# 2_Microcontroller.net
KiCad netlist of a schematic drawn in Altium Designer
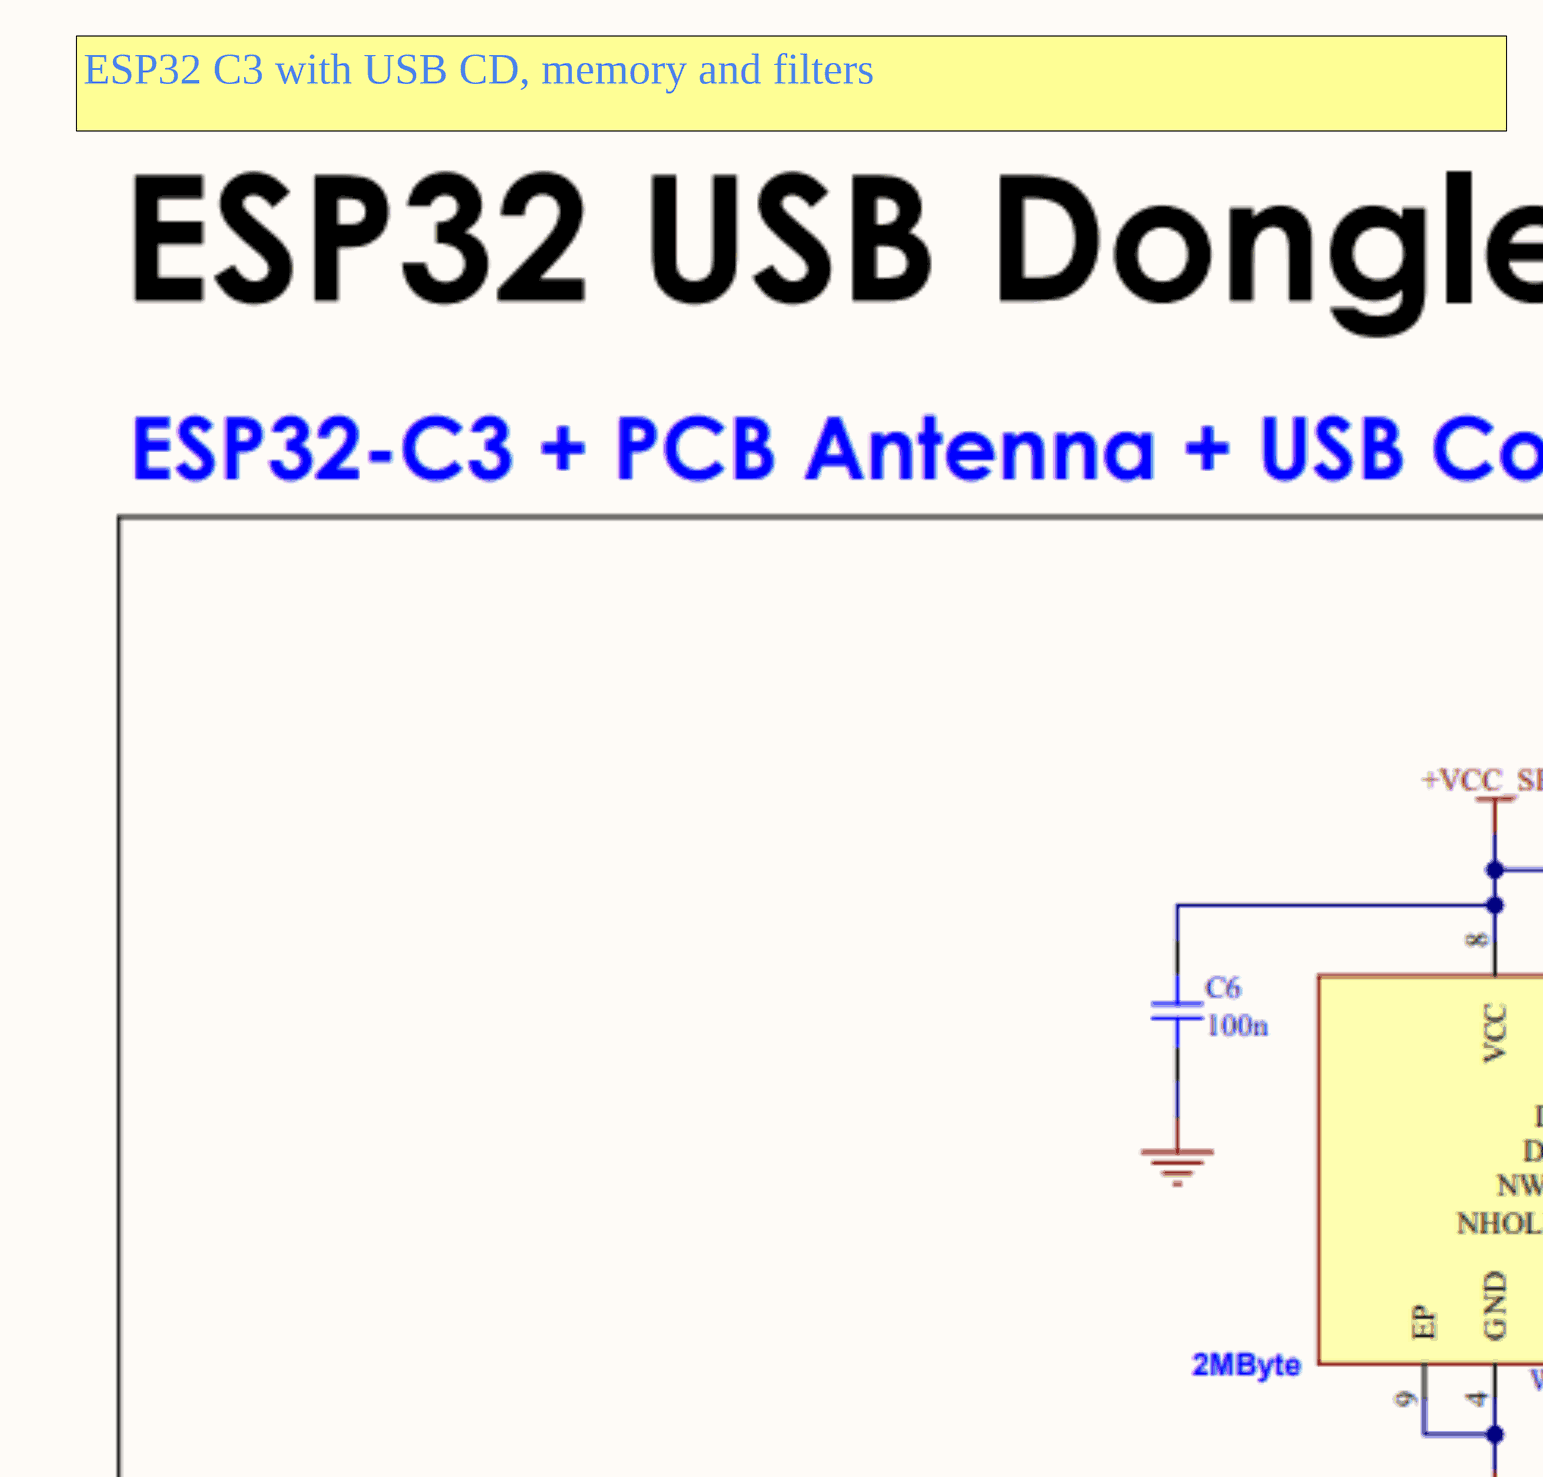
[diagram p0: 2_Microcontroller.SchDoc, top right]
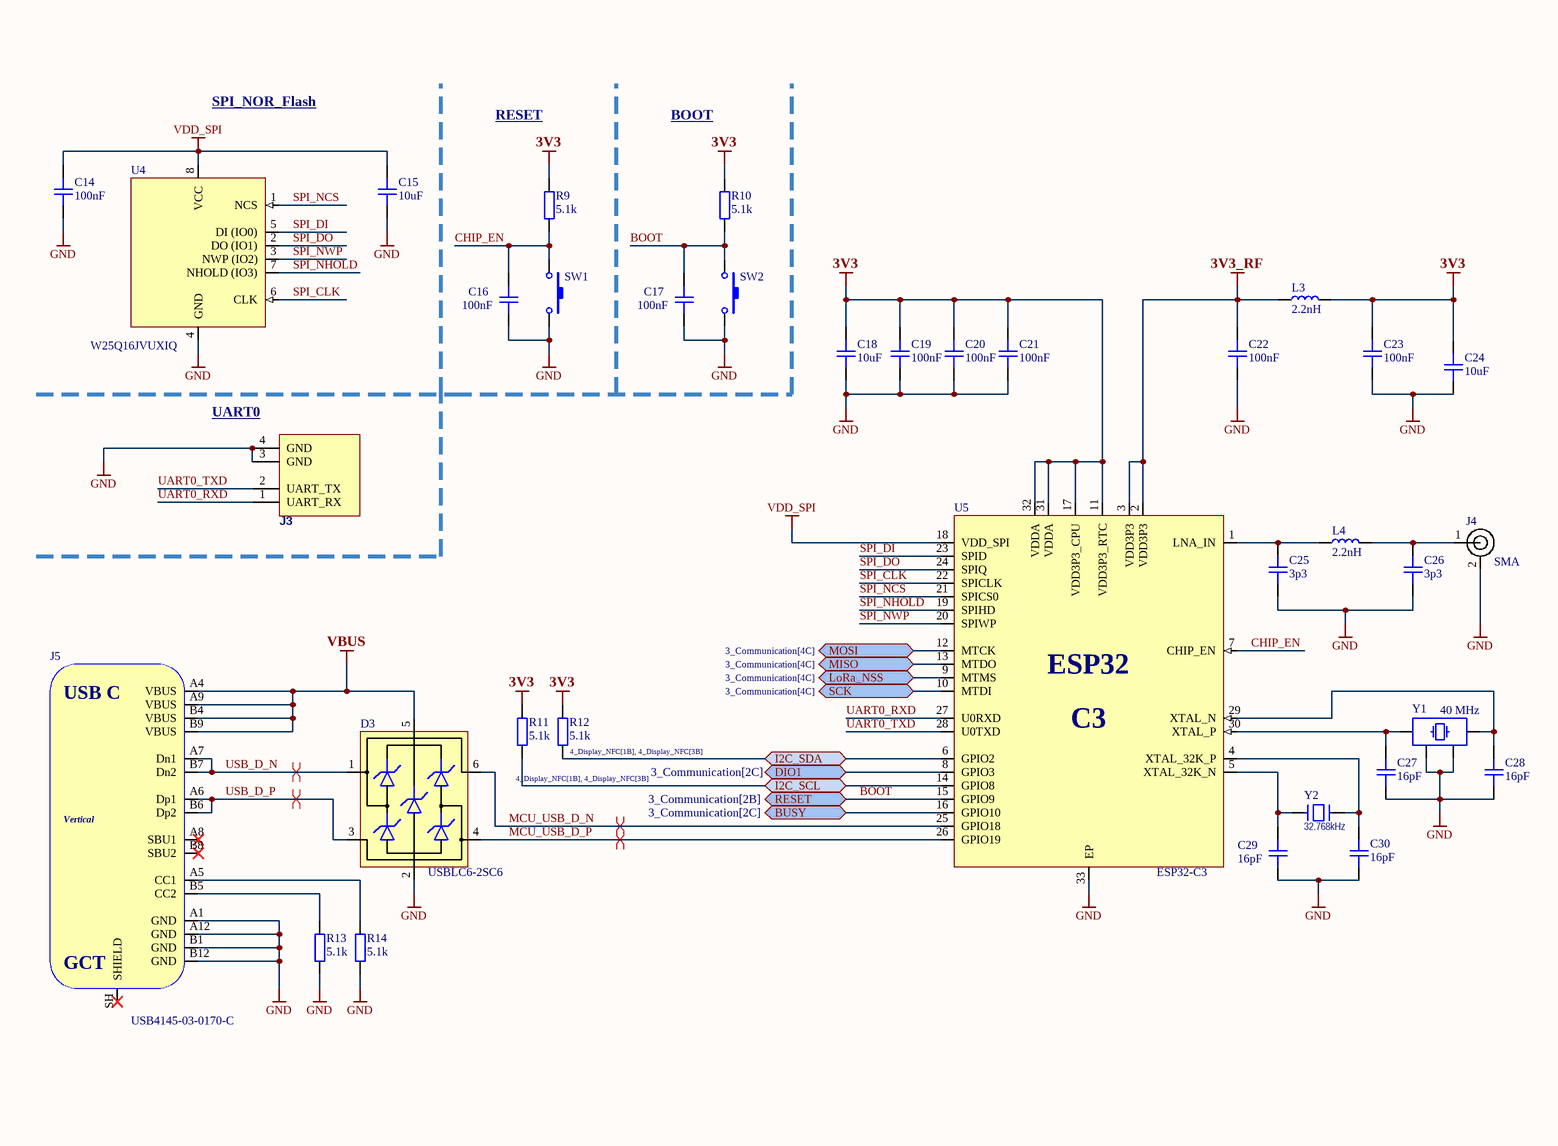
[diagram p1: 2_Microcontroller.SchDoc, bottom left]
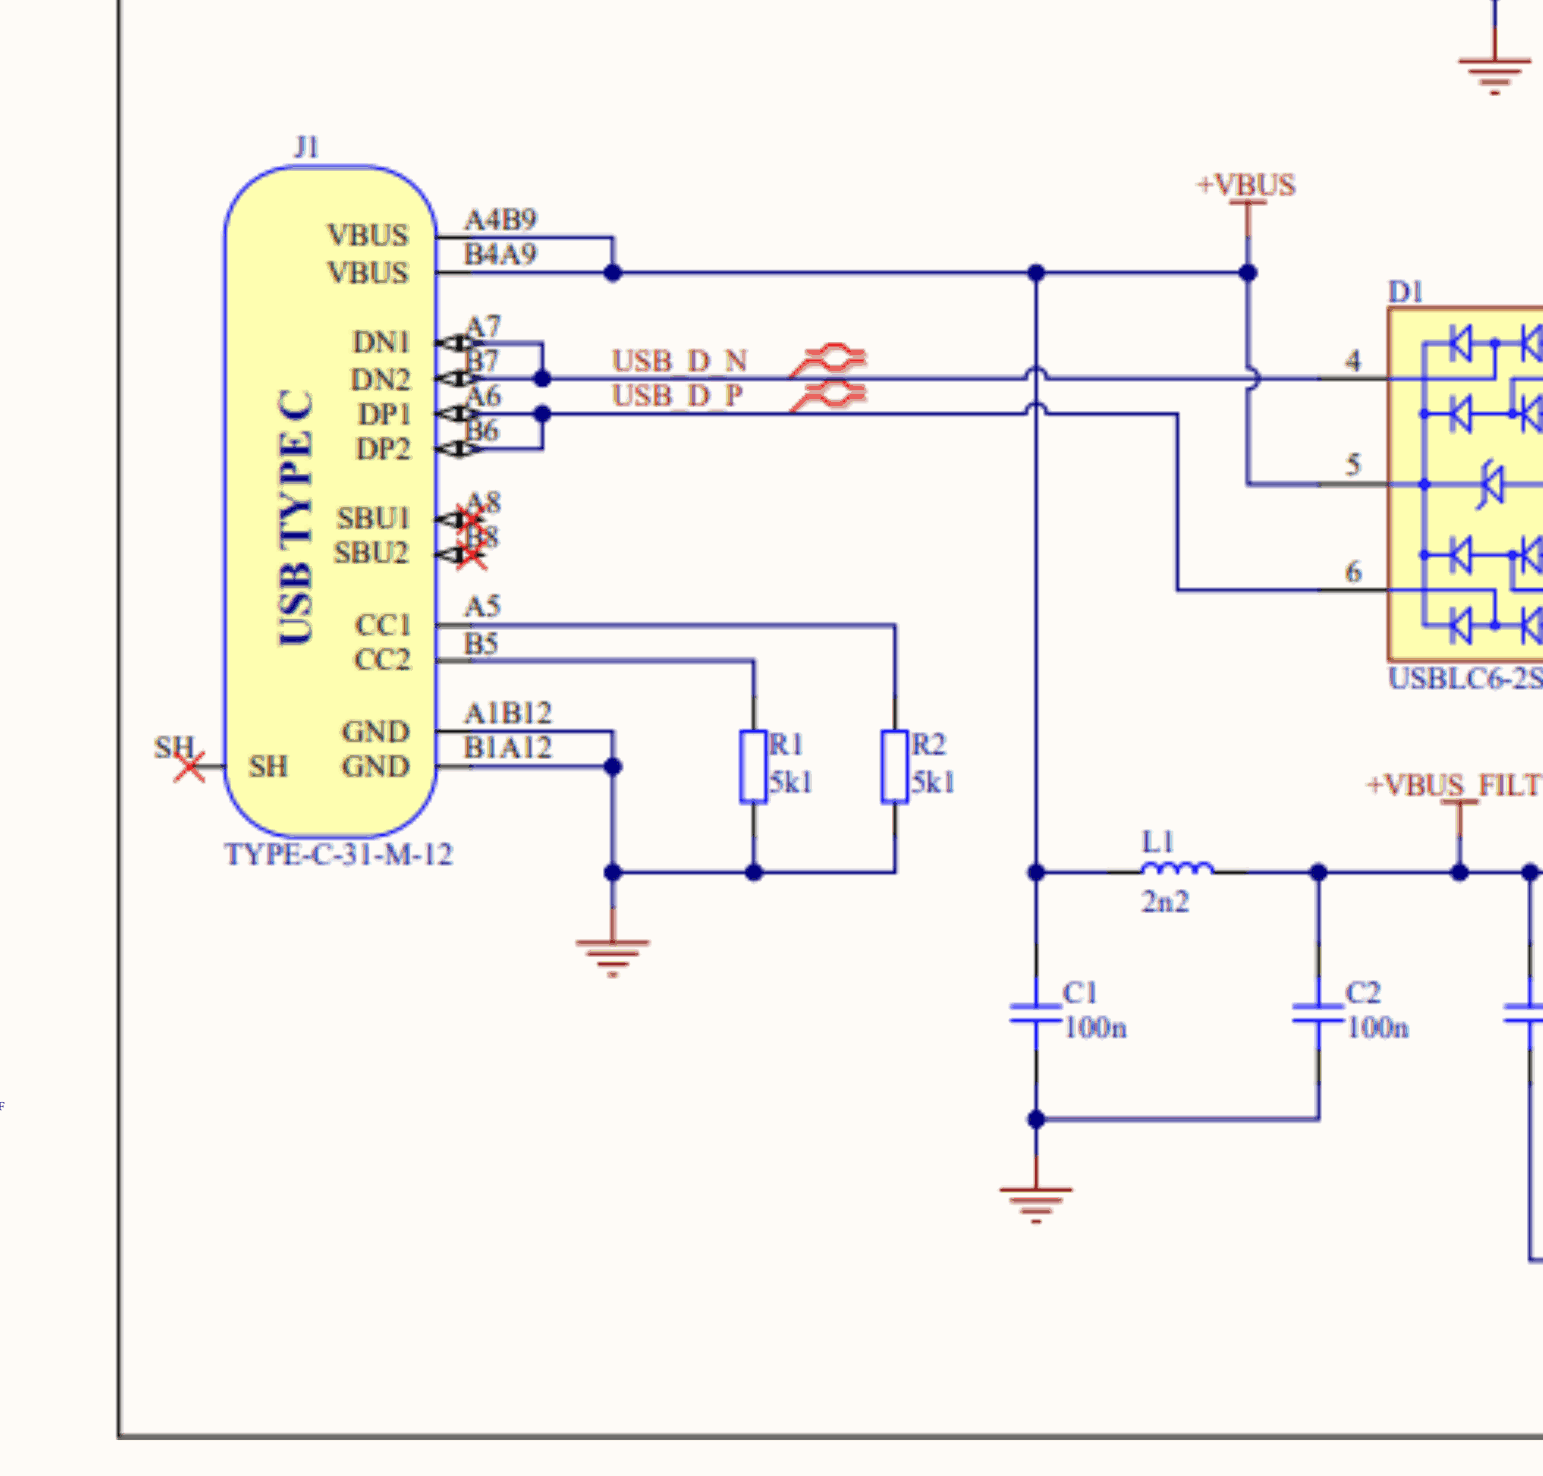
[diagram p2: 2_Microcontroller.SchDoc, bottom right]

(export (version "E")
  (design (tool "Eeschema 10.0.6"))
  (components
    (comp (ref "C14")
      (value "100nF")
      (footprint "C0603")
      (description "Capacitor SMD 0603")
      (libsource (lib "Schlib1") (part "CAP_0603"))
    )
    (comp (ref "C15")
      (value "10uF")
      (footprint "C0805")
      (description "Capacitor SMD 0805")
      (libsource (lib "Schlib1") (part "CAP_0805"))
    )
    (comp (ref "C16")
      (value "100nF")
      (footprint "C0603")
      (description "Capacitor SMD 0603")
      (libsource (lib "Schlib1") (part "CAP_0603"))
    )
    (comp (ref "C17")
      (value "100nF")
      (footprint "C0603")
      (description "Capacitor SMD 0603")
      (libsource (lib "Schlib1") (part "CAP_0603"))
    )
    (comp (ref "C18")
      (value "10uF")
      (footprint "C0805")
      (description "Capacitor SMD 0805")
      (libsource (lib "Schlib1") (part "CAP_0805"))
    )
    (comp (ref "C19")
      (value "100nF")
      (footprint "C0603")
      (description "Capacitor SMD 0603")
      (libsource (lib "Schlib1") (part "CAP_0603"))
    )
    (comp (ref "C20")
      (value "100nF")
      (footprint "C0603")
      (description "Capacitor SMD 0603")
      (libsource (lib "Schlib1") (part "CAP_0603"))
    )
    (comp (ref "C21")
      (value "100nF")
      (footprint "C0603")
      (description "Capacitor SMD 0603")
      (libsource (lib "Schlib1") (part "CAP_0603"))
    )
    (comp (ref "C22")
      (value "100nF")
      (footprint "C0603")
      (description "Capacitor SMD 0603")
      (libsource (lib "Schlib1") (part "CAP_0603"))
    )
    (comp (ref "C23")
      (value "100nF")
      (footprint "C0603")
      (description "Capacitor SMD 0603")
      (libsource (lib "Schlib1") (part "CAP_0603"))
    )
    (comp (ref "C24")
      (value "10uF")
      (footprint "C0805")
      (description "Capacitor SMD 0805")
      (libsource (lib "Schlib1") (part "CAP_0805"))
    )
    (comp (ref "C25")
      (value "3p3")
      (footprint "C0603")
      (description "Capacitor SMD 0603")
      (libsource (lib "Schlib1") (part "CAP_0603"))
    )
    (comp (ref "C26")
      (value "3p3")
      (footprint "C0603")
      (description "Capacitor SMD 0603")
      (libsource (lib "Schlib1") (part "CAP_0603"))
    )
    (comp (ref "C27")
      (value "16pF")
      (footprint "C0603")
      (description "Capacitor SMD 0603")
      (libsource (lib "Schlib1") (part "CAP_0603"))
    )
    (comp (ref "C28")
      (value "16pF")
      (footprint "C0603")
      (description "Capacitor SMD 0603")
      (libsource (lib "Schlib1") (part "CAP_0603"))
    )
    (comp (ref "C29")
      (value "16pF")
      (footprint "C0603")
      (description "Capacitor SMD 0603")
      (libsource (lib "Schlib1") (part "CAP_0603"))
    )
    (comp (ref "C30")
      (value "16pF")
      (footprint "C0603")
      (description "Capacitor SMD 0603")
      (libsource (lib "Schlib1") (part "CAP_0603"))
    )
    (comp (ref "D3")
      (value "USBLC6-2SC6")
      (footprint "SOT23-6")
      (description "Low-Capacitance ESD Protection USB")
      (fields (field (name "MANUFACTURER") "STMicroelectronics"))
      (libsource (lib "Schlib1") (part "USBLC6-2SC6"))
    )
    (comp (ref "J3")
      (value "Header1x4")
      (footprint "HEADER_2x2_2.54")
      (libsource (lib "Schlib1") (part "Header1x4"))
    )
    (comp (ref "J4")
      (value "SMA")
      (footprint "CON_SMA-EDGE-S")
      (description "RF Connector SMA Female 50 Ohms 18 GHz PCB Edge Mount")
      (fields
        (field (name "MANUFACTURER") "RF Solutions")
        (field (name "MANUFACTURER PART NUMBER") "CON-SMA-EDGE-S")
      )
      (libsource (lib "Schlib1") (part "CON-SMA-EDGE-S"))
    )
    (comp (ref "J5")
      (value "USB4145-03-0170-C")
      (footprint "VALCON_CSP-USC16-TR")
      (description "USB Connector Type C SMT 16 Pin Vertical")
      (fields (field (name "MANUFACTURER") "GCT"))
      (libsource (lib "Schlib1") (part "USB4145-03-0170-C"))
    )
    (comp (ref "L3")
      (value "2.2nH")
      (footprint "L0603")
      (description "Inductor SMD 1008")
      (libsource (lib "Schlib1") (part "IND_1008"))
    )
    (comp (ref "L4")
      (value "2.2nH")
      (footprint "L0603")
      (description "Inductor SMD 1008")
      (libsource (lib "Schlib1") (part "IND_1008"))
    )
    (comp (ref "R9")
      (value "5.1k")
      (footprint "R0603")
      (description "Resistor SMD 0603")
      (libsource (lib "Schlib1") (part "RES_0603"))
    )
    (comp (ref "R10")
      (value "5.1k")
      (footprint "R0603")
      (description "Resistor SMD 0603")
      (libsource (lib "Schlib1") (part "RES_0603"))
    )
    (comp (ref "R11")
      (value "5.1k")
      (footprint "R0603")
      (description "Resistor SMD 0603")
      (libsource (lib "Schlib1") (part "RES_0603"))
    )
    (comp (ref "R12")
      (value "5.1k")
      (footprint "R0603")
      (description "Resistor SMD 0603")
      (libsource (lib "Schlib1") (part "RES_0603"))
    )
    (comp (ref "R13")
      (value "5.1k")
      (footprint "R0603")
      (description "Resistor SMD 0603")
      (libsource (lib "Schlib1") (part "RES_0603"))
    )
    (comp (ref "R14")
      (value "5.1k")
      (footprint "R0603")
      (description "Resistor SMD 0603")
      (libsource (lib "Schlib1") (part "RES_0603"))
    )
    (comp (ref "SW1")
      (value "PTS645SM43SMTR92 LFS")
      (footprint "SW_SKRPACE010")
      (description "Switch")
      (fields (field (name "PUBLISHER") "Altium Limited"))
      (libsource (lib "Schlib1") (part "SW-PB"))
    )
    (comp (ref "SW2")
      (value "PTS645SM43SMTR92 LFS")
      (footprint "SW_SKRPACE010")
      (description "Switch")
      (fields (field (name "PUBLISHER") "Altium Limited"))
      (libsource (lib "Schlib1") (part "SW-PB"))
    )
    (comp (ref "U4")
      (value "W25Q16JVUXIQ")
      (footprint "SOIC-8N_208mil")
      (description "16M-BIT SERIAL FLASH MEMORY WITH DUAL/QUAD SPI USON-8")
      (fields (field (name "MANUFACTURER") "Winbond"))
      (libsource (lib "Schlib1") (part "W25Q16JVUXIQ"))
    )
    (comp (ref "U5")
      (value "ESP32-C3")
      (footprint "QFN-32-5x5x0.85mm")
      (fields (field (name "MANUFACTURER") "Espressif"))
      (libsource (lib "Schlib1") (part "ESP32-C3"))
    )
    (comp (ref "Y1")
      (value "40 MHz")
      (footprint "CRYSTAL_ECX-32_3.2x2.5x0.8 - duplicate")
      (description "Crystal SMD 4-Pin 3225x4")
      (libsource (lib "Schlib1") (part "XTAL_2016"))
    )
    (comp (ref "Y2")
      (value "32.768kHz")
      (footprint "CRYSTAL_SX-3215")
      (description "Crystal")
      (libsource (lib "Schlib1") (part "CRYSTAL_1"))
    )
  )
  (nets
    (net (code "1") (name "/BOOT") (class "Default")
      (node (ref "C17") (pin "2") (pinfunction "2_2") (pintype "passive"))
      (node (ref "R10") (pin "1") (pinfunction "1_1") (pintype "passive"))
      (node (ref "SW2") (pin "1") (pinfunction "1_1") (pintype "passive"))
      (node (ref "U5") (pin "15") (pinfunction "GPIO9_15") (pintype "bidirectional"))
    )
    (net (code "2") (name "/BUSY") (class "Default")
      (node (ref "U5") (pin "16") (pinfunction "GPIO10_16") (pintype "bidirectional"))
    )
    (net (code "3") (name "/CHIP_EN") (class "Default")
      (node (ref "C16") (pin "2") (pinfunction "2_2") (pintype "passive"))
      (node (ref "R9") (pin "1") (pinfunction "1_1") (pintype "passive"))
      (node (ref "SW1") (pin "1") (pinfunction "1_1") (pintype "passive"))
      (node (ref "U5") (pin "7") (pinfunction "CHIP_EN_7") (pintype "input"))
    )
    (net (code "4") (name "/DIO1") (class "Default")
      (node (ref "U5") (pin "8") (pinfunction "GPIO3_8") (pintype "bidirectional"))
    )
    (net (code "5") (name "/I2C_SCL") (class "Default")
      (node (ref "R11") (pin "1") (pinfunction "1_1") (pintype "passive"))
      (node (ref "U5") (pin "14") (pinfunction "GPIO8_14") (pintype "bidirectional"))
    )
    (net (code "6") (name "/I2C_SDA") (class "Default")
      (node (ref "R12") (pin "1") (pinfunction "1_1") (pintype "passive"))
      (node (ref "U5") (pin "6") (pinfunction "GPIO2_6") (pintype "bidirectional"))
    )
    (net (code "7") (name "/LoRa_NSS") (class "Default")
      (node (ref "U5") (pin "9") (pinfunction "MTMS_9") (pintype "bidirectional"))
    )
    (net (code "8") (name "/MCU_USB_D_N") (class "Default")
      (node (ref "D3") (pin "6") (pinfunction "IO1_6") (pintype "passive"))
      (node (ref "U5") (pin "25") (pinfunction "GPIO18_25") (pintype "passive"))
    )
    (net (code "9") (name "/MCU_USB_D_P") (class "Default")
      (node (ref "D3") (pin "4") (pinfunction "IO2_4") (pintype "passive"))
      (node (ref "U5") (pin "26") (pinfunction "GPIO19_26") (pintype "passive"))
    )
    (net (code "10") (name "/MISO") (class "Default")
      (node (ref "U5") (pin "13") (pinfunction "MTDO_13") (pintype "bidirectional"))
    )
    (net (code "11") (name "/MOSI") (class "Default")
      (node (ref "U5") (pin "12") (pinfunction "MTCK_12") (pintype "bidirectional"))
    )
    (net (code "12") (name "/SCK") (class "Default")
      (node (ref "U5") (pin "10") (pinfunction "MTDI_10") (pintype "bidirectional"))
    )
    (net (code "13") (name "/SPI_CLK") (class "Default")
      (node (ref "U4") (pin "6") (pinfunction "CLK_6") (pintype "input"))
      (node (ref "U5") (pin "22") (pinfunction "SPICLK_22") (pintype "bidirectional"))
    )
    (net (code "14") (name "/SPI_DI") (class "Default")
      (node (ref "U4") (pin "5") (pinfunction "DI_(IO0)_5") (pintype "bidirectional"))
      (node (ref "U5") (pin "23") (pinfunction "SPID_23") (pintype "bidirectional"))
    )
    (net (code "15") (name "/SPI_DO") (class "Default")
      (node (ref "U4") (pin "2") (pinfunction "DO_(IO1)_2") (pintype "bidirectional"))
      (node (ref "U5") (pin "24") (pinfunction "SPIQ_24") (pintype "bidirectional"))
    )
    (net (code "16") (name "/SPI_NCS") (class "Default")
      (node (ref "U4") (pin "1") (pinfunction "NCS_1") (pintype "input"))
      (node (ref "U5") (pin "21") (pinfunction "SPICS0_21") (pintype "bidirectional"))
    )
    (net (code "17") (name "/SPI_NHOLD") (class "Default")
      (node (ref "U4") (pin "7") (pinfunction "NHOLD_(IO3)_7") (pintype "bidirectional"))
      (node (ref "U5") (pin "19") (pinfunction "SPIHD_19") (pintype "bidirectional"))
    )
    (net (code "18") (name "/SPI_NWP") (class "Default")
      (node (ref "U4") (pin "3") (pinfunction "NWP_(IO2)_3") (pintype "bidirectional"))
      (node (ref "U5") (pin "20") (pinfunction "SPIWP_20") (pintype "bidirectional"))
    )
    (net (code "19") (name "/UART0_RXD") (class "Default")
      (node (ref "J3") (pin "1") (pinfunction "UART_RX_1") (pintype "passive"))
      (node (ref "U5") (pin "27") (pinfunction "U0RXD_27") (pintype "bidirectional"))
    )
    (net (code "20") (name "/UART0_TXD") (class "Default")
      (node (ref "J3") (pin "2") (pinfunction "UART_TX_2") (pintype "passive"))
      (node (ref "U5") (pin "28") (pinfunction "U0TXD_28") (pintype "bidirectional"))
    )
    (net (code "21") (name "/USB_D_N") (class "Default")
      (node (ref "D3") (pin "1") (pinfunction "IO1_1") (pintype "passive"))
      (node (ref "J5") (pin "A7") (pinfunction "Dn1_A7") (pintype "passive"))
      (node (ref "J5") (pin "B7") (pinfunction "Dn2_B7") (pintype "passive"))
    )
    (net (code "22") (name "/USB_D_P") (class "Default")
      (node (ref "D3") (pin "3") (pinfunction "IO2_3") (pintype "passive"))
      (node (ref "J5") (pin "A6") (pinfunction "Dp1_A6") (pintype "passive"))
      (node (ref "J5") (pin "B6") (pinfunction "Dp2_B6") (pintype "passive"))
    )
    (net (code "23") (name "3V3") (class "Default")
      (node (ref "C18") (pin "2") (pinfunction "2_2") (pintype "passive"))
      (node (ref "C19") (pin "2") (pinfunction "2_2") (pintype "passive"))
      (node (ref "C20") (pin "2") (pinfunction "2_2") (pintype "passive"))
      (node (ref "C21") (pin "2") (pinfunction "2_2") (pintype "passive"))
      (node (ref "C23") (pin "2") (pinfunction "2_2") (pintype "passive"))
      (node (ref "C24") (pin "2") (pinfunction "2_2") (pintype "passive"))
      (node (ref "L3") (pin "2") (pinfunction "2_2") (pintype "passive"))
      (node (ref "R10") (pin "2") (pinfunction "2_2") (pintype "passive"))
      (node (ref "R11") (pin "2") (pinfunction "2_2") (pintype "passive"))
      (node (ref "R12") (pin "2") (pinfunction "2_2") (pintype "passive"))
      (node (ref "R9") (pin "2") (pinfunction "2_2") (pintype "passive"))
      (node (ref "U5") (pin "11") (pinfunction "VDD3P3_RTC_11") (pintype "power_in"))
      (node (ref "U5") (pin "17") (pinfunction "VDD3P3_CPU_17") (pintype "power_in"))
      (node (ref "U5") (pin "31") (pinfunction "VDDA_31") (pintype "power_in"))
      (node (ref "U5") (pin "32") (pinfunction "VDDA_32") (pintype "power_in"))
    )
    (net (code "24") (name "3V3_RF") (class "Default")
      (node (ref "C22") (pin "2") (pinfunction "2_2") (pintype "passive"))
      (node (ref "L3") (pin "1") (pinfunction "1_1") (pintype "passive"))
      (node (ref "U5") (pin "2") (pinfunction "VDD3P3_2") (pintype "power_in"))
      (node (ref "U5") (pin "3") (pinfunction "VDD3P3_3") (pintype "power_in"))
    )
    (net (code "25") (name "GND") (class "Default")
      (node (ref "C14") (pin "1") (pinfunction "1_1") (pintype "passive"))
      (node (ref "C15") (pin "1") (pinfunction "1_1") (pintype "passive"))
      (node (ref "C16") (pin "1") (pinfunction "1_1") (pintype "passive"))
      (node (ref "C17") (pin "1") (pinfunction "1_1") (pintype "passive"))
      (node (ref "C18") (pin "1") (pinfunction "1_1") (pintype "passive"))
      (node (ref "C19") (pin "1") (pinfunction "1_1") (pintype "passive"))
      (node (ref "C20") (pin "1") (pinfunction "1_1") (pintype "passive"))
      (node (ref "C21") (pin "1") (pinfunction "1_1") (pintype "passive"))
      (node (ref "C22") (pin "1") (pinfunction "1_1") (pintype "passive"))
      (node (ref "C23") (pin "1") (pinfunction "1_1") (pintype "passive"))
      (node (ref "C24") (pin "1") (pinfunction "1_1") (pintype "passive"))
      (node (ref "C25") (pin "1") (pinfunction "1_1") (pintype "passive"))
      (node (ref "C26") (pin "1") (pinfunction "1_1") (pintype "passive"))
      (node (ref "C27") (pin "1") (pinfunction "1_1") (pintype "passive"))
      (node (ref "C28") (pin "1") (pinfunction "1_1") (pintype "passive"))
      (node (ref "C29") (pin "1") (pinfunction "1_1") (pintype "passive"))
      (node (ref "C30") (pin "1") (pinfunction "1_1") (pintype "passive"))
      (node (ref "D3") (pin "2") (pinfunction "GND_2") (pintype "power_in"))
      (node (ref "J3") (pin "3") (pinfunction "GND_3") (pintype "passive"))
      (node (ref "J3") (pin "4") (pinfunction "GND_4") (pintype "passive"))
      (node (ref "J4") (pin "2") (pinfunction "2_2") (pintype "passive"))
      (node (ref "J5") (pin "A1") (pinfunction "GND_A1") (pintype "passive"))
      (node (ref "J5") (pin "A12") (pinfunction "GND_A12") (pintype "passive"))
      (node (ref "J5") (pin "B1") (pinfunction "GND_B1") (pintype "passive"))
      (node (ref "J5") (pin "B12") (pinfunction "GND_B12") (pintype "passive"))
      (node (ref "R13") (pin "1") (pinfunction "1_1") (pintype "passive"))
      (node (ref "R14") (pin "1") (pinfunction "1_1") (pintype "passive"))
      (node (ref "SW1") (pin "2") (pinfunction "2_2") (pintype "passive"))
      (node (ref "SW2") (pin "2") (pinfunction "2_2") (pintype "passive"))
      (node (ref "U4") (pin "4") (pinfunction "GND_4") (pintype "power_in"))
      (node (ref "U5") (pin "33") (pinfunction "EP_33") (pintype "power_in"))
      (node (ref "Y1") (pin "2") (pinfunction "2_2") (pintype "passive"))
      (node (ref "Y1") (pin "4") (pinfunction "4_4") (pintype "passive"))
    )
    (net (code "26") (name "Net-(C26-Pad2)") (class "Default")
      (node (ref "C26") (pin "2") (pinfunction "2_2") (pintype "passive"))
      (node (ref "J4") (pin "1") (pinfunction "1_1") (pintype "passive"))
      (node (ref "L4") (pin "2") (pinfunction "2_2") (pintype "passive"))
    )
    (net (code "27") (name "Net-(J5-CC1)") (class "Default")
      (node (ref "J5") (pin "A5") (pinfunction "CC1_A5") (pintype "passive"))
      (node (ref "R14") (pin "2") (pinfunction "2_2") (pintype "passive"))
    )
    (net (code "28") (name "Net-(J5-CC2)") (class "Default")
      (node (ref "J5") (pin "B5") (pinfunction "CC2_B5") (pintype "passive"))
      (node (ref "R13") (pin "2") (pinfunction "2_2") (pintype "passive"))
    )
    (net (code "29") (name "Net-(U5-LNA_IN)") (class "Default")
      (node (ref "C25") (pin "2") (pinfunction "2_2") (pintype "passive"))
      (node (ref "L4") (pin "1") (pinfunction "1_1") (pintype "passive"))
      (node (ref "U5") (pin "1") (pinfunction "LNA_IN_1") (pintype "bidirectional"))
    )
    (net (code "30") (name "Net-(U5-XTAL_32K_N)") (class "Default")
      (node (ref "C29") (pin "2") (pinfunction "2_2") (pintype "passive"))
      (node (ref "U5") (pin "5") (pinfunction "XTAL_32K_N_5") (pintype "bidirectional"))
      (node (ref "Y2") (pin "2") (pinfunction "2_2") (pintype "passive"))
    )
    (net (code "31") (name "Net-(U5-XTAL_32K_P)") (class "Default")
      (node (ref "C30") (pin "2") (pinfunction "2_2") (pintype "passive"))
      (node (ref "U5") (pin "4") (pinfunction "XTAL_32K_P_4") (pintype "bidirectional"))
      (node (ref "Y2") (pin "1") (pinfunction "1_1") (pintype "passive"))
    )
    (net (code "32") (name "Net-(U5-XTAL_N)") (class "Default")
      (node (ref "C28") (pin "2") (pinfunction "2_2") (pintype "passive"))
      (node (ref "U5") (pin "29") (pinfunction "XTAL_N_29") (pintype "input"))
      (node (ref "Y1") (pin "3") (pinfunction "3_3") (pintype "passive"))
    )
    (net (code "33") (name "Net-(U5-XTAL_P)") (class "Default")
      (node (ref "C27") (pin "2") (pinfunction "2_2") (pintype "passive"))
      (node (ref "U5") (pin "30") (pinfunction "XTAL_P_30") (pintype "input"))
      (node (ref "Y1") (pin "1") (pinfunction "1_1") (pintype "passive"))
    )
    (net (code "34") (name "VBUS") (class "Default")
      (node (ref "D3") (pin "5") (pinfunction "VBUS_5") (pintype "power_in"))
      (node (ref "J5") (pin "A4") (pinfunction "VBUS_A4") (pintype "passive"))
      (node (ref "J5") (pin "A9") (pinfunction "VBUS_A9") (pintype "passive"))
      (node (ref "J5") (pin "B4") (pinfunction "VBUS_B4") (pintype "passive"))
      (node (ref "J5") (pin "B9") (pinfunction "VBUS_B9") (pintype "passive"))
    )
    (net (code "35") (name "VDD_SPI") (class "Default")
      (node (ref "C14") (pin "2") (pinfunction "2_2") (pintype "passive"))
      (node (ref "C15") (pin "2") (pinfunction "2_2") (pintype "passive"))
      (node (ref "U4") (pin "8") (pinfunction "VCC_8") (pintype "power_in"))
      (node (ref "U5") (pin "18") (pinfunction "VDD_SPI_18") (pintype "power_in"))
    )
    (net (code "36") (name "unconnected-(J5-SBU1-PadA8)") (class "Default")
      (node (ref "J5") (pin "A8") (pinfunction "SBU1_A8") (pintype "passive+no_connect"))
    )
    (net (code "37") (name "unconnected-(J5-SBU2-PadB8)") (class "Default")
      (node (ref "J5") (pin "B8") (pinfunction "SBU2_B8") (pintype "passive+no_connect"))
    )
    (net (code "38") (name "unconnected-(J5-SHIELD-PadSH)") (class "Default")
      (node (ref "J5") (pin "SH") (pinfunction "SHIELD_SH") (pintype "passive+no_connect"))
    )
  )
)
